# protoboard.net
KiCad netlist of a schematic drawn in EAGLE
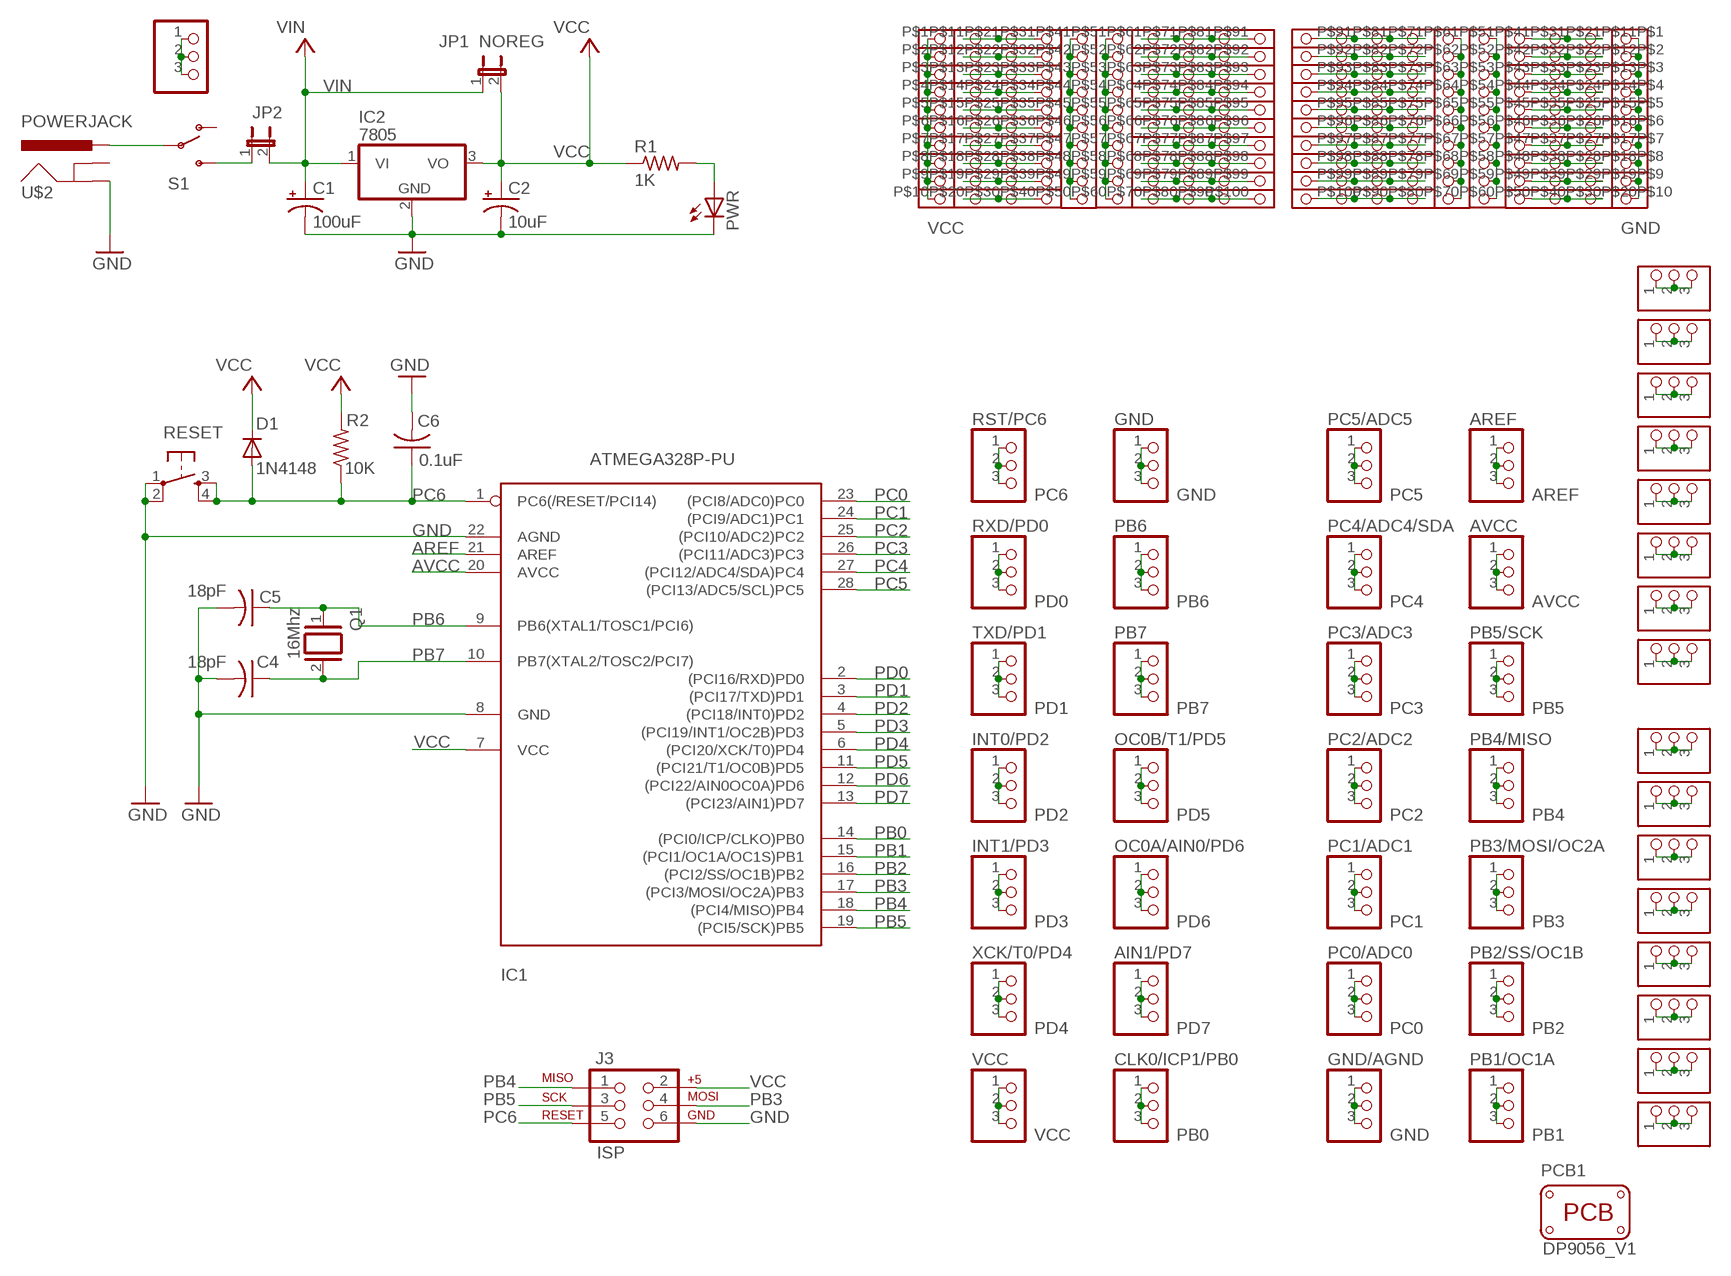
[diagram p0: schematic, sheet 1]

(export (version "E")
  (design (tool "Eeschema 10.0.6"))
  (components
    (comp (ref "AIN1/PD7")
      (value "PINHD-1X3")
      (footprint "eagle-import:1X03")
      (libsource (lib "eagle-import") (part "PINHD-1X3"))
    )
    (comp (ref "AREF")
      (value "PINHD-1X3")
      (footprint "eagle-import:1X03")
      (libsource (lib "eagle-import") (part "PINHD-1X3"))
    )
    (comp (ref "AVCC")
      (value "PINHD-1X3")
      (footprint "eagle-import:1X03")
      (libsource (lib "eagle-import") (part "PINHD-1X3"))
    )
    (comp (ref "C1")
      (value "100uF")
      (footprint "eagle-import:CPOL-RADIAL-100UF-25V")
      (libsource (lib "eagle-import") (part "CAP_POLPTH1"))
    )
    (comp (ref "C2")
      (value "10uF")
      (footprint "eagle-import:CPOL-RADIAL-10UF-25V")
      (libsource (lib "eagle-import") (part "CAP_POLPTH2"))
    )
    (comp (ref "C4")
      (value "18pF")
      (footprint "eagle-import:C025-025X050")
      (libsource (lib "eagle-import") (part "C-US025-025X050"))
    )
    (comp (ref "C5")
      (value "18pF")
      (footprint "eagle-import:C025-025X050")
      (libsource (lib "eagle-import") (part "C-US025-025X050"))
    )
    (comp (ref "C6")
      (value "0.1uF")
      (footprint "eagle-import:C025-025X050")
      (libsource (lib "eagle-import") (part "C-US025-025X050"))
    )
    (comp (ref "CLK0/ICP1/PB0")
      (value "PINHD-1X3")
      (footprint "eagle-import:1X03")
      (libsource (lib "eagle-import") (part "PINHD-1X3"))
    )
    (comp (ref "D1")
      (value "1N4148")
      (footprint "eagle-import:DIODE-1N4148")
      (libsource (lib "eagle-import") (part "DIODE1N4148"))
    )
    (comp (ref "GND")
      (value "PINHD-1X3")
      (footprint "eagle-import:1X03")
      (libsource (lib "eagle-import") (part "PINHD-1X3"))
    )
    (comp (ref "GND/AGND")
      (value "PINHD-1X3")
      (footprint "eagle-import:1X03")
      (libsource (lib "eagle-import") (part "PINHD-1X3"))
    )
    (comp (ref "IC1")
      (value "ATMEGA328P-PU")
      (footprint "eagle-import:DIL28-3")
      (libsource (lib "eagle-import") (part "ATMEGA168P-20"))
    )
    (comp (ref "IC2")
      (value "7805")
      (footprint "eagle-import:TO220H")
      (libsource (lib "eagle-import") (part "78T05"))
    )
    (comp (ref "INT0/PD2")
      (value "PINHD-1X3")
      (footprint "eagle-import:1X03")
      (libsource (lib "eagle-import") (part "PINHD-1X3"))
    )
    (comp (ref "INT1/PD3")
      (value "PINHD-1X3")
      (footprint "eagle-import:1X03")
      (libsource (lib "eagle-import") (part "PINHD-1X3"))
    )
    (comp (ref "J3")
      (value "ISP")
      (footprint "eagle-import:2X3")
      (libsource (lib "eagle-import") (part "AVR_SPI_PRG_6PTH"))
    )
    (comp (ref "JP1")
      (value "NOREG")
      (footprint "eagle-import:1X02")
      (libsource (lib "eagle-import") (part "JUMPER-2PTH"))
    )
    (comp (ref "JP2")
      (value "TP1")
      (footprint "eagle-import:1X02")
      (libsource (lib "eagle-import") (part "JUMPER-2PTH"))
    )
    (comp (ref "OC0A/AIN0/PD6")
      (value "PINHD-1X3")
      (footprint "eagle-import:1X03")
      (libsource (lib "eagle-import") (part "PINHD-1X3"))
    )
    (comp (ref "OC0B/T1/PD5")
      (value "PINHD-1X3")
      (footprint "eagle-import:1X03")
      (libsource (lib "eagle-import") (part "PINHD-1X3"))
    )
    (comp (ref "PB1/OC1A")
      (value "PINHD-1X3")
      (footprint "eagle-import:1X03")
      (libsource (lib "eagle-import") (part "PINHD-1X3"))
    )
    (comp (ref "PB2/SS/OC1B")
      (value "PINHD-1X3")
      (footprint "eagle-import:1X03")
      (libsource (lib "eagle-import") (part "PINHD-1X3"))
    )
    (comp (ref "PB3/MOSI/OC2A")
      (value "PINHD-1X3")
      (footprint "eagle-import:1X03")
      (libsource (lib "eagle-import") (part "PINHD-1X3"))
    )
    (comp (ref "PB4/MISO")
      (value "PINHD-1X3")
      (footprint "eagle-import:1X03")
      (libsource (lib "eagle-import") (part "PINHD-1X3"))
    )
    (comp (ref "PB5/SCK")
      (value "PINHD-1X3")
      (footprint "eagle-import:1X03")
      (libsource (lib "eagle-import") (part "PINHD-1X3"))
    )
    (comp (ref "PB6")
      (value "PINHD-1X3")
      (footprint "eagle-import:1X03")
      (libsource (lib "eagle-import") (part "PINHD-1X3"))
    )
    (comp (ref "PB7")
      (value "PINHD-1X3")
      (footprint "eagle-import:1X03")
      (libsource (lib "eagle-import") (part "PINHD-1X3"))
    )
    (comp (ref "PC0/ADC0")
      (value "PINHD-1X3")
      (footprint "eagle-import:1X03")
      (libsource (lib "eagle-import") (part "PINHD-1X3"))
    )
    (comp (ref "PC1/ADC1")
      (value "PINHD-1X3")
      (footprint "eagle-import:1X03")
      (libsource (lib "eagle-import") (part "PINHD-1X3"))
    )
    (comp (ref "PC2/ADC2")
      (value "PINHD-1X3")
      (footprint "eagle-import:1X03")
      (libsource (lib "eagle-import") (part "PINHD-1X3"))
    )
    (comp (ref "PC3/ADC3")
      (value "PINHD-1X3")
      (footprint "eagle-import:1X03")
      (libsource (lib "eagle-import") (part "PINHD-1X3"))
    )
    (comp (ref "PC4/ADC4/SDA")
      (value "PINHD-1X3")
      (footprint "eagle-import:1X03")
      (libsource (lib "eagle-import") (part "PINHD-1X3"))
    )
    (comp (ref "PC5/ADC5")
      (value "PINHD-1X3")
      (footprint "eagle-import:1X03")
      (libsource (lib "eagle-import") (part "PINHD-1X3"))
    )
    (comp (ref "PCB1")
      (value "PCB_DP_RECTANGLE-56X90")
      (footprint "eagle-import:DP9056_V1")
      (libsource (lib "eagle-import") (part "PCB_DP_RECTANGLE-56X90"))
    )
    (comp (ref "PWR")
      (value "LED3MM")
      (footprint "eagle-import:LED3MM")
      (libsource (lib "eagle-import") (part "LED3MM"))
    )
    (comp (ref "Q1")
      (value "16Mhz")
      (footprint "eagle-import:QS")
      (libsource (lib "eagle-import") (part "XTAL/S"))
    )
    (comp (ref "R1")
      (value "1K")
      (footprint "eagle-import:0207_7")
      (libsource (lib "eagle-import") (part "RESISTOR-1/4W"))
    )
    (comp (ref "R2")
      (value "10K")
      (footprint "eagle-import:0207_7")
      (libsource (lib "eagle-import") (part "RESISTOR-1/4W"))
    )
    (comp (ref "RESET")
      (value "TAC_SWITCHPTH")
      (footprint "eagle-import:TACTILE-PTH")
      (libsource (lib "eagle-import") (part "TAC_SWITCHPTH"))
    )
    (comp (ref "RST/PC6")
      (value "PINHD-1X3")
      (footprint "eagle-import:1X03")
      (libsource (lib "eagle-import") (part "PINHD-1X3"))
    )
    (comp (ref "RXD/PD0")
      (value "PINHD-1X3")
      (footprint "eagle-import:1X03")
      (libsource (lib "eagle-import") (part "PINHD-1X3"))
    )
    (comp (ref "S1")
      (value "SWITCH-SPDTPTH")
      (footprint "eagle-import:SWITCH-SPDT")
      (libsource (lib "eagle-import") (part "SWITCH-SPDTPTH"))
    )
    (comp (ref "TXD/PD1")
      (value "PINHD-1X3")
      (footprint "eagle-import:1X03")
      (libsource (lib "eagle-import") (part "PINHD-1X3"))
    )
    (comp (ref "U$1")
      (value "PROTOFIELD-10X10")
      (footprint "eagle-import:PROTOFIELD-10X10")
      (libsource (lib "eagle-import") (part "PROTOFIELD-10X10"))
    )
    (comp (ref "U$2")
      (value "POWERJACK")
      (footprint "eagle-import:POWERJACK_SLOT")
      (libsource (lib "eagle-import") (part "POWERJACK"))
    )
    (comp (ref "U$3")
      (value "PROTOFIELD-10X10")
      (footprint "eagle-import:PROTOFIELD-10X10")
      (libsource (lib "eagle-import") (part "PROTOFIELD-10X10"))
    )
    (comp (ref "U$4")
      (value "PROTOFIELD-3")
      (footprint "eagle-import:PROTOFIELD-3")
      (libsource (lib "eagle-import") (part "PROTOFIELD-3"))
    )
    (comp (ref "U$5")
      (value "PROTOFIELD-3")
      (footprint "eagle-import:PROTOFIELD-3")
      (libsource (lib "eagle-import") (part "PROTOFIELD-3"))
    )
    (comp (ref "U$6")
      (value "PROTOFIELD-3")
      (footprint "eagle-import:PROTOFIELD-3")
      (libsource (lib "eagle-import") (part "PROTOFIELD-3"))
    )
    (comp (ref "U$7")
      (value "PROTOFIELD-3")
      (footprint "eagle-import:PROTOFIELD-3")
      (libsource (lib "eagle-import") (part "PROTOFIELD-3"))
    )
    (comp (ref "U$8")
      (value "PROTOFIELD-3")
      (footprint "eagle-import:PROTOFIELD-3")
      (libsource (lib "eagle-import") (part "PROTOFIELD-3"))
    )
    (comp (ref "U$9")
      (value "PROTOFIELD-3")
      (footprint "eagle-import:PROTOFIELD-3")
      (libsource (lib "eagle-import") (part "PROTOFIELD-3"))
    )
    (comp (ref "U$10")
      (value "PROTOFIELD-3")
      (footprint "eagle-import:PROTOFIELD-3")
      (libsource (lib "eagle-import") (part "PROTOFIELD-3"))
    )
    (comp (ref "U$11")
      (value "PROTOFIELD-3")
      (footprint "eagle-import:PROTOFIELD-3")
      (libsource (lib "eagle-import") (part "PROTOFIELD-3"))
    )
    (comp (ref "U$12")
      (value "PROTOFIELD-3")
      (footprint "eagle-import:PROTOFIELD-3")
      (libsource (lib "eagle-import") (part "PROTOFIELD-3"))
    )
    (comp (ref "U$13")
      (value "PROTOFIELD-3")
      (footprint "eagle-import:PROTOFIELD-3")
      (libsource (lib "eagle-import") (part "PROTOFIELD-3"))
    )
    (comp (ref "U$14")
      (value "PROTOFIELD-3")
      (footprint "eagle-import:PROTOFIELD-3")
      (libsource (lib "eagle-import") (part "PROTOFIELD-3"))
    )
    (comp (ref "U$15")
      (value "PROTOFIELD-3")
      (footprint "eagle-import:PROTOFIELD-3")
      (libsource (lib "eagle-import") (part "PROTOFIELD-3"))
    )
    (comp (ref "U$16")
      (value "PROTOFIELD-3")
      (footprint "eagle-import:PROTOFIELD-3")
      (libsource (lib "eagle-import") (part "PROTOFIELD-3"))
    )
    (comp (ref "U$17")
      (value "PROTOFIELD-3")
      (footprint "eagle-import:PROTOFIELD-3")
      (libsource (lib "eagle-import") (part "PROTOFIELD-3"))
    )
    (comp (ref "U$18")
      (value "PROTOFIELD-3")
      (footprint "eagle-import:PROTOFIELD-3")
      (libsource (lib "eagle-import") (part "PROTOFIELD-3"))
    )
    (comp (ref "U$19")
      (value "PROTOFIELD-3")
      (footprint "eagle-import:PROTOFIELD-3")
      (libsource (lib "eagle-import") (part "PROTOFIELD-3"))
    )
    (comp (ref "VCC")
      (value "PINHD-1X3")
      (footprint "eagle-import:1X03")
      (libsource (lib "eagle-import") (part "PINHD-1X3"))
    )
    (comp (ref "VIN_")
      (value "PINHD-1X3")
      (footprint "eagle-import:1X03")
      (libsource (lib "eagle-import") (part "PINHD-1X3"))
    )
    (comp (ref "XCK/T0/PD4")
      (value "PINHD-1X3")
      (footprint "eagle-import:1X03")
      (libsource (lib "eagle-import") (part "PINHD-1X3"))
    )
  )
  (nets
    (net (code "1") (name "/AREF") (class "Default")
      (node (ref "AREF") (pin "1") (pinfunction "1_1") (pintype "passive"))
      (node (ref "AREF") (pin "2") (pinfunction "2_2") (pintype "passive"))
      (node (ref "AREF") (pin "3") (pinfunction "3_3") (pintype "passive"))
      (node (ref "IC1") (pin "21") (pinfunction "AREF_21") (pintype "bidirectional"))
    )
    (net (code "2") (name "/AVCC") (class "Default")
      (node (ref "AVCC") (pin "1") (pinfunction "1_1") (pintype "passive"))
      (node (ref "AVCC") (pin "2") (pinfunction "2_2") (pintype "passive"))
      (node (ref "AVCC") (pin "3") (pinfunction "3_3") (pintype "passive"))
      (node (ref "IC1") (pin "20") (pinfunction "AVCC_20") (pintype "bidirectional"))
    )
    (net (code "3") (name "/PB0") (class "Default")
      (node (ref "CLK0/ICP1/PB0") (pin "1") (pinfunction "1_1") (pintype "passive"))
      (node (ref "CLK0/ICP1/PB0") (pin "2") (pinfunction "2_2") (pintype "passive"))
      (node (ref "CLK0/ICP1/PB0") (pin "3") (pinfunction "3_3") (pintype "passive"))
      (node (ref "IC1") (pin "14") (pinfunction "(PCI0/ICP/CLKO)PB0_14") (pintype "bidirectional"))
    )
    (net (code "4") (name "/PB1") (class "Default")
      (node (ref "IC1") (pin "15") (pinfunction "(PCI1/OC1A/OC1S)PB1_15") (pintype "bidirectional"))
      (node (ref "PB1/OC1A") (pin "1") (pinfunction "1_1") (pintype "passive"))
      (node (ref "PB1/OC1A") (pin "2") (pinfunction "2_2") (pintype "passive"))
      (node (ref "PB1/OC1A") (pin "3") (pinfunction "3_3") (pintype "passive"))
    )
    (net (code "5") (name "/PB2") (class "Default")
      (node (ref "IC1") (pin "16") (pinfunction "(PCI2/SS/OC1B)PB2_16") (pintype "bidirectional"))
      (node (ref "PB2/SS/OC1B") (pin "1") (pinfunction "1_1") (pintype "passive"))
      (node (ref "PB2/SS/OC1B") (pin "2") (pinfunction "2_2") (pintype "passive"))
      (node (ref "PB2/SS/OC1B") (pin "3") (pinfunction "3_3") (pintype "passive"))
    )
    (net (code "6") (name "/PB3") (class "Default")
      (node (ref "IC1") (pin "17") (pinfunction "(PCI3/MOSI/OC2A)PB3_17") (pintype "bidirectional"))
      (node (ref "J3") (pin "4") (pinfunction "4_4") (pintype "passive"))
      (node (ref "PB3/MOSI/OC2A") (pin "1") (pinfunction "1_1") (pintype "passive"))
      (node (ref "PB3/MOSI/OC2A") (pin "2") (pinfunction "2_2") (pintype "passive"))
      (node (ref "PB3/MOSI/OC2A") (pin "3") (pinfunction "3_3") (pintype "passive"))
    )
    (net (code "7") (name "/PB4") (class "Default")
      (node (ref "IC1") (pin "18") (pinfunction "(PCI4/MISO)PB4_18") (pintype "bidirectional"))
      (node (ref "J3") (pin "1") (pinfunction "1_1") (pintype "passive"))
      (node (ref "PB4/MISO") (pin "1") (pinfunction "1_1") (pintype "passive"))
      (node (ref "PB4/MISO") (pin "2") (pinfunction "2_2") (pintype "passive"))
      (node (ref "PB4/MISO") (pin "3") (pinfunction "3_3") (pintype "passive"))
    )
    (net (code "8") (name "/PB5") (class "Default")
      (node (ref "IC1") (pin "19") (pinfunction "(PCI5/SCK)PB5_19") (pintype "bidirectional"))
      (node (ref "J3") (pin "3") (pinfunction "3_3") (pintype "passive"))
      (node (ref "PB5/SCK") (pin "1") (pinfunction "1_1") (pintype "passive"))
      (node (ref "PB5/SCK") (pin "2") (pinfunction "2_2") (pintype "passive"))
      (node (ref "PB5/SCK") (pin "3") (pinfunction "3_3") (pintype "passive"))
    )
    (net (code "9") (name "/PB6") (class "Default")
      (node (ref "C5") (pin "1") (pinfunction "1_1") (pintype "passive"))
      (node (ref "IC1") (pin "9") (pinfunction "PB6(XTAL1/TOSC1/PCI6)_9") (pintype "bidirectional"))
      (node (ref "PB6") (pin "1") (pinfunction "1_1") (pintype "passive"))
      (node (ref "PB6") (pin "2") (pinfunction "2_2") (pintype "passive"))
      (node (ref "PB6") (pin "3") (pinfunction "3_3") (pintype "passive"))
      (node (ref "Q1") (pin "1") (pinfunction "1_1") (pintype "passive"))
    )
    (net (code "10") (name "/PB7") (class "Default")
      (node (ref "C4") (pin "1") (pinfunction "1_1") (pintype "passive"))
      (node (ref "IC1") (pin "10") (pinfunction "PB7(XTAL2/TOSC2/PCI7)_10") (pintype "bidirectional"))
      (node (ref "PB7") (pin "1") (pinfunction "1_1") (pintype "passive"))
      (node (ref "PB7") (pin "2") (pinfunction "2_2") (pintype "passive"))
      (node (ref "PB7") (pin "3") (pinfunction "3_3") (pintype "passive"))
      (node (ref "Q1") (pin "2") (pinfunction "2_2") (pintype "passive"))
    )
    (net (code "11") (name "/PC0") (class "Default")
      (node (ref "IC1") (pin "23") (pinfunction "(PCI8/ADC0)PC0_23") (pintype "bidirectional"))
      (node (ref "PC0/ADC0") (pin "1") (pinfunction "1_1") (pintype "passive"))
      (node (ref "PC0/ADC0") (pin "2") (pinfunction "2_2") (pintype "passive"))
      (node (ref "PC0/ADC0") (pin "3") (pinfunction "3_3") (pintype "passive"))
    )
    (net (code "12") (name "/PC1") (class "Default")
      (node (ref "IC1") (pin "24") (pinfunction "(PCI9/ADC1)PC1_24") (pintype "bidirectional"))
      (node (ref "PC1/ADC1") (pin "1") (pinfunction "1_1") (pintype "passive"))
      (node (ref "PC1/ADC1") (pin "2") (pinfunction "2_2") (pintype "passive"))
      (node (ref "PC1/ADC1") (pin "3") (pinfunction "3_3") (pintype "passive"))
    )
    (net (code "13") (name "/PC2") (class "Default")
      (node (ref "IC1") (pin "25") (pinfunction "(PCI10/ADC2)PC2_25") (pintype "bidirectional"))
      (node (ref "PC2/ADC2") (pin "1") (pinfunction "1_1") (pintype "passive"))
      (node (ref "PC2/ADC2") (pin "2") (pinfunction "2_2") (pintype "passive"))
      (node (ref "PC2/ADC2") (pin "3") (pinfunction "3_3") (pintype "passive"))
    )
    (net (code "14") (name "/PC3") (class "Default")
      (node (ref "IC1") (pin "26") (pinfunction "(PCI11/ADC3)PC3_26") (pintype "bidirectional"))
      (node (ref "PC3/ADC3") (pin "1") (pinfunction "1_1") (pintype "passive"))
      (node (ref "PC3/ADC3") (pin "2") (pinfunction "2_2") (pintype "passive"))
      (node (ref "PC3/ADC3") (pin "3") (pinfunction "3_3") (pintype "passive"))
    )
    (net (code "15") (name "/PC4") (class "Default")
      (node (ref "IC1") (pin "27") (pinfunction "(PCI12/ADC4/SDA)PC4_27") (pintype "bidirectional"))
      (node (ref "PC4/ADC4/SDA") (pin "1") (pinfunction "1_1") (pintype "passive"))
      (node (ref "PC4/ADC4/SDA") (pin "2") (pinfunction "2_2") (pintype "passive"))
      (node (ref "PC4/ADC4/SDA") (pin "3") (pinfunction "3_3") (pintype "passive"))
    )
    (net (code "16") (name "/PC5") (class "Default")
      (node (ref "IC1") (pin "28") (pinfunction "(PCI13/ADC5/SCL)PC5_28") (pintype "bidirectional"))
      (node (ref "PC5/ADC5") (pin "1") (pinfunction "1_1") (pintype "passive"))
      (node (ref "PC5/ADC5") (pin "2") (pinfunction "2_2") (pintype "passive"))
      (node (ref "PC5/ADC5") (pin "3") (pinfunction "3_3") (pintype "passive"))
    )
    (net (code "17") (name "/PC6") (class "Default")
      (node (ref "C6") (pin "1") (pinfunction "1_1") (pintype "passive"))
      (node (ref "D1") (pin "A") (pinfunction "A_A") (pintype "passive"))
      (node (ref "IC1") (pin "1") (pinfunction "PC6(/RESET/PCI14)_1") (pintype "bidirectional"))
      (node (ref "J3") (pin "5") (pinfunction "5_5") (pintype "passive"))
      (node (ref "R2") (pin "1") (pinfunction "1_1") (pintype "passive"))
      (node (ref "RESET") (pin "3") (pinfunction "3_3") (pintype "passive"))
      (node (ref "RESET") (pin "4") (pinfunction "4_4") (pintype "passive"))
      (node (ref "RST/PC6") (pin "1") (pinfunction "1_1") (pintype "passive"))
      (node (ref "RST/PC6") (pin "2") (pinfunction "2_2") (pintype "passive"))
      (node (ref "RST/PC6") (pin "3") (pinfunction "3_3") (pintype "passive"))
    )
    (net (code "18") (name "/PD0") (class "Default")
      (node (ref "IC1") (pin "2") (pinfunction "(PCI16/RXD)PD0_2") (pintype "bidirectional"))
      (node (ref "RXD/PD0") (pin "1") (pinfunction "1_1") (pintype "passive"))
      (node (ref "RXD/PD0") (pin "2") (pinfunction "2_2") (pintype "passive"))
      (node (ref "RXD/PD0") (pin "3") (pinfunction "3_3") (pintype "passive"))
    )
    (net (code "19") (name "/PD1") (class "Default")
      (node (ref "IC1") (pin "3") (pinfunction "(PCI17/TXD)PD1_3") (pintype "bidirectional"))
      (node (ref "TXD/PD1") (pin "1") (pinfunction "1_1") (pintype "passive"))
      (node (ref "TXD/PD1") (pin "2") (pinfunction "2_2") (pintype "passive"))
      (node (ref "TXD/PD1") (pin "3") (pinfunction "3_3") (pintype "passive"))
    )
    (net (code "20") (name "/PD2") (class "Default")
      (node (ref "IC1") (pin "4") (pinfunction "(PCI18/INT0)PD2_4") (pintype "bidirectional"))
      (node (ref "INT0/PD2") (pin "1") (pinfunction "1_1") (pintype "passive"))
      (node (ref "INT0/PD2") (pin "2") (pinfunction "2_2") (pintype "passive"))
      (node (ref "INT0/PD2") (pin "3") (pinfunction "3_3") (pintype "passive"))
    )
    (net (code "21") (name "/PD3") (class "Default")
      (node (ref "IC1") (pin "5") (pinfunction "(PCI19/INT1/OC2B)PD3_5") (pintype "bidirectional"))
      (node (ref "INT1/PD3") (pin "1") (pinfunction "1_1") (pintype "passive"))
      (node (ref "INT1/PD3") (pin "2") (pinfunction "2_2") (pintype "passive"))
      (node (ref "INT1/PD3") (pin "3") (pinfunction "3_3") (pintype "passive"))
    )
    (net (code "22") (name "/PD4") (class "Default")
      (node (ref "IC1") (pin "6") (pinfunction "(PCI20/XCK/T0)PD4_6") (pintype "bidirectional"))
      (node (ref "XCK/T0/PD4") (pin "1") (pinfunction "1_1") (pintype "passive"))
      (node (ref "XCK/T0/PD4") (pin "2") (pinfunction "2_2") (pintype "passive"))
      (node (ref "XCK/T0/PD4") (pin "3") (pinfunction "3_3") (pintype "passive"))
    )
    (net (code "23") (name "/PD5") (class "Default")
      (node (ref "IC1") (pin "11") (pinfunction "(PCI21/T1/OC0B)PD5_11") (pintype "bidirectional"))
      (node (ref "OC0B/T1/PD5") (pin "1") (pinfunction "1_1") (pintype "passive"))
      (node (ref "OC0B/T1/PD5") (pin "2") (pinfunction "2_2") (pintype "passive"))
      (node (ref "OC0B/T1/PD5") (pin "3") (pinfunction "3_3") (pintype "passive"))
    )
    (net (code "24") (name "/PD6") (class "Default")
      (node (ref "IC1") (pin "12") (pinfunction "(PCI22/AIN0OC0A)PD6_12") (pintype "bidirectional"))
      (node (ref "OC0A/AIN0/PD6") (pin "1") (pinfunction "1_1") (pintype "passive"))
      (node (ref "OC0A/AIN0/PD6") (pin "2") (pinfunction "2_2") (pintype "passive"))
      (node (ref "OC0A/AIN0/PD6") (pin "3") (pinfunction "3_3") (pintype "passive"))
    )
    (net (code "25") (name "/PD7") (class "Default")
      (node (ref "AIN1/PD7") (pin "1") (pinfunction "1_1") (pintype "passive"))
      (node (ref "AIN1/PD7") (pin "2") (pinfunction "2_2") (pintype "passive"))
      (node (ref "AIN1/PD7") (pin "3") (pinfunction "3_3") (pintype "passive"))
      (node (ref "IC1") (pin "13") (pinfunction "(PCI23/AIN1)PD7_13") (pintype "bidirectional"))
    )
    (net (code "26") (name "GND") (class "Default")
      (node (ref "C1") (pin "2") (pinfunction "-_2") (pintype "passive"))
      (node (ref "C2") (pin "2") (pinfunction "-_2") (pintype "passive"))
      (node (ref "C4") (pin "2") (pinfunction "2_2") (pintype "passive"))
      (node (ref "C5") (pin "2") (pinfunction "2_2") (pintype "passive"))
      (node (ref "C6") (pin "2") (pinfunction "2_2") (pintype "passive"))
      (node (ref "GND") (pin "1") (pinfunction "1_1") (pintype "passive"))
      (node (ref "GND") (pin "2") (pinfunction "2_2") (pintype "passive"))
      (node (ref "GND") (pin "3") (pinfunction "3_3") (pintype "passive"))
      (node (ref "GND/AGND") (pin "1") (pinfunction "1_1") (pintype "passive"))
      (node (ref "GND/AGND") (pin "2") (pinfunction "2_2") (pintype "passive"))
      (node (ref "GND/AGND") (pin "3") (pinfunction "3_3") (pintype "passive"))
      (node (ref "IC1") (pin "22") (pinfunction "AGND_22") (pintype "bidirectional"))
      (node (ref "IC1") (pin "8") (pinfunction "GND_8") (pintype "bidirectional"))
      (node (ref "IC2") (pin "2") (pinfunction "GND_2") (pintype "passive"))
      (node (ref "J3") (pin "6") (pinfunction "6_6") (pintype "passive"))
      (node (ref "PWR") (pin "K") (pinfunction "C_K") (pintype "passive"))
      (node (ref "RESET") (pin "1") (pinfunction "1_1") (pintype "passive"))
      (node (ref "RESET") (pin "2") (pinfunction "2_2") (pintype "passive"))
      (node (ref "U$2") (pin "GND@1") (pinfunction "GND_GND@1") (pintype "bidirectional"))
      (node (ref "U$3") (pin "P$1") (pinfunction "1_P$1") (pintype "passive"))
      (node (ref "U$3") (pin "P$10") (pinfunction "P$10_P$10") (pintype "passive"))
      (node (ref "U$3") (pin "P$2") (pinfunction "5_P$2") (pintype "passive"))
      (node (ref "U$3") (pin "P$3") (pinfunction "P$3_P$3") (pintype "passive"))
      (node (ref "U$3") (pin "P$4") (pinfunction "P$4_P$4") (pintype "passive"))
      (node (ref "U$3") (pin "P$5") (pinfunction "P$5_P$5") (pintype "passive"))
      (node (ref "U$3") (pin "P$6") (pinfunction "P$6_P$6") (pintype "passive"))
      (node (ref "U$3") (pin "P$7") (pinfunction "P$7_P$7") (pintype "passive"))
      (node (ref "U$3") (pin "P$8") (pinfunction "P$8_P$8") (pintype "passive"))
      (node (ref "U$3") (pin "P$9") (pinfunction "P$9_P$9") (pintype "passive"))
    )
    (net (code "27") (name "Net-(PWR-PadA)") (class "Default")
      (node (ref "PWR") (pin "A") (pinfunction "A_A") (pintype "passive"))
      (node (ref "R1") (pin "2") (pinfunction "2_2") (pintype "passive"))
    )
    (net (code "28") (name "Net-(S1-P)") (class "Default")
      (node (ref "S1") (pin "2") (pinfunction "P_2") (pintype "passive"))
      (node (ref "U$2") (pin "PWR") (pinfunction "PWR_PWR") (pintype "bidirectional"))
    )
    (net (code "29") (name "Net-(S1-S)") (class "Default")
      (node (ref "JP2") (pin "1") (pinfunction "1_1") (pintype "passive"))
      (node (ref "S1") (pin "3") (pinfunction "S_3") (pintype "passive"))
    )
    (net (code "30") (name "Net-(U$1-2)") (class "Default")
      (node (ref "U$1") (pin "P$11") (pinfunction "2_P$11") (pintype "passive"))
      (node (ref "U$1") (pin "P$21") (pinfunction "3_P$21") (pintype "passive"))
      (node (ref "U$1") (pin "P$31") (pinfunction "4_P$31") (pintype "passive"))
    )
    (net (code "31") (name "Net-(U$1-6)") (class "Default")
      (node (ref "U$1") (pin "P$12") (pinfunction "6_P$12") (pintype "passive"))
      (node (ref "U$1") (pin "P$22") (pinfunction "7_P$22") (pintype "passive"))
      (node (ref "U$1") (pin "P$32") (pinfunction "8_P$32") (pintype "passive"))
    )
    (net (code "32") (name "Net-(U$1-PadP$13)") (class "Default")
      (node (ref "U$1") (pin "P$13") (pinfunction "P$13_P$13") (pintype "passive"))
      (node (ref "U$1") (pin "P$23") (pinfunction "P$23_P$23") (pintype "passive"))
      (node (ref "U$1") (pin "P$33") (pinfunction "P$33_P$33") (pintype "passive"))
    )
    (net (code "33") (name "Net-(U$1-PadP$14)") (class "Default")
      (node (ref "U$1") (pin "P$14") (pinfunction "P$14_P$14") (pintype "passive"))
      (node (ref "U$1") (pin "P$24") (pinfunction "P$24_P$24") (pintype "passive"))
      (node (ref "U$1") (pin "P$34") (pinfunction "P$34_P$34") (pintype "passive"))
    )
    (net (code "34") (name "Net-(U$1-PadP$15)") (class "Default")
      (node (ref "U$1") (pin "P$15") (pinfunction "P$15_P$15") (pintype "passive"))
      (node (ref "U$1") (pin "P$25") (pinfunction "P$25_P$25") (pintype "passive"))
      (node (ref "U$1") (pin "P$35") (pinfunction "P$35_P$35") (pintype "passive"))
    )
    (net (code "35") (name "Net-(U$1-PadP$16)") (class "Default")
      (node (ref "U$1") (pin "P$16") (pinfunction "P$16_P$16") (pintype "passive"))
      (node (ref "U$1") (pin "P$26") (pinfunction "P$26_P$26") (pintype "passive"))
      (node (ref "U$1") (pin "P$36") (pinfunction "P$36_P$36") (pintype "passive"))
    )
    (net (code "36") (name "Net-(U$1-PadP$17)") (class "Default")
      (node (ref "U$1") (pin "P$17") (pinfunction "P$17_P$17") (pintype "passive"))
      (node (ref "U$1") (pin "P$27") (pinfunction "P$27_P$27") (pintype "passive"))
      (node (ref "U$1") (pin "P$37") (pinfunction "P$37_P$37") (pintype "passive"))
    )
    (net (code "37") (name "Net-(U$1-PadP$18)") (class "Default")
      (node (ref "U$1") (pin "P$18") (pinfunction "P$18_P$18") (pintype "passive"))
      (node (ref "U$1") (pin "P$28") (pinfunction "P$28_P$28") (pintype "passive"))
      (node (ref "U$1") (pin "P$38") (pinfunction "P$38_P$38") (pintype "passive"))
    )
    (net (code "38") (name "Net-(U$1-PadP$19)") (class "Default")
      (node (ref "U$1") (pin "P$19") (pinfunction "P$19_P$19") (pintype "passive"))
      (node (ref "U$1") (pin "P$29") (pinfunction "P$29_P$29") (pintype "passive"))
      (node (ref "U$1") (pin "P$39") (pinfunction "P$39_P$39") (pintype "passive"))
    )
    (net (code "39") (name "Net-(U$1-PadP$20)") (class "Default")
      (node (ref "U$1") (pin "P$20") (pinfunction "P$20_P$20") (pintype "passive"))
      (node (ref "U$1") (pin "P$30") (pinfunction "P$30_P$30") (pintype "passive"))
      (node (ref "U$1") (pin "P$40") (pinfunction "P$40_P$40") (pintype "passive"))
    )
    (net (code "40") (name "Net-(U$1-PadP$41)") (class "Default")
      (node (ref "U$1") (pin "P$41") (pinfunction "P$41_P$41") (pintype "passive"))
      (node (ref "U$1") (pin "P$42") (pinfunction "P$42_P$42") (pintype "passive"))
      (node (ref "U$1") (pin "P$43") (pinfunction "P$43_P$43") (pintype "passive"))
      (node (ref "U$1") (pin "P$44") (pinfunction "P$44_P$44") (pintype "passive"))
      (node (ref "U$1") (pin "P$45") (pinfunction "P$45_P$45") (pintype "passive"))
      (node (ref "U$1") (pin "P$46") (pinfunction "P$46_P$46") (pintype "passive"))
      (node (ref "U$1") (pin "P$47") (pinfunction "P$47_P$47") (pintype "passive"))
      (node (ref "U$1") (pin "P$48") (pinfunction "P$48_P$48") (pintype "passive"))
      (node (ref "U$1") (pin "P$49") (pinfunction "P$49_P$49") (pintype "passive"))
      (node (ref "U$1") (pin "P$50") (pinfunction "P$50_P$50") (pintype "passive"))
    )
    (net (code "41") (name "Net-(U$1-PadP$51)") (class "Default")
      (node (ref "U$1") (pin "P$51") (pinfunction "P$51_P$51") (pintype "passive"))
      (node (ref "U$1") (pin "P$52") (pinfunction "P$52_P$52") (pintype "passive"))
      (node (ref "U$1") (pin "P$53") (pinfunction "P$53_P$53") (pintype "passive"))
      (node (ref "U$1") (pin "P$54") (pinfunction "P$54_P$54") (pintype "passive"))
      (node (ref "U$1") (pin "P$55") (pinfunction "P$55_P$55") (pintype "passive"))
      (node (ref "U$1") (pin "P$56") (pinfunction "P$56_P$56") (pintype "passive"))
      (node (ref "U$1") (pin "P$57") (pinfunction "P$57_P$57") (pintype "passive"))
      (node (ref "U$1") (pin "P$58") (pinfunction "P$58_P$58") (pintype "passive"))
      (node (ref "U$1") (pin "P$59") (pinfunction "P$59_P$59") (pintype "passive"))
      (node (ref "U$1") (pin "P$60") (pinfunction "P$60_P$60") (pintype "passive"))
    )
    (net (code "42") (name "Net-(U$1-PadP$61)") (class "Default")
      (node (ref "U$1") (pin "P$61") (pinfunction "P$61_P$61") (pintype "passive"))
      (node (ref "U$1") (pin "P$71") (pinfunction "P$71_P$71") (pintype "passive"))
      (node (ref "U$1") (pin "P$81") (pinfunction "P$81_P$81") (pintype "passive"))
      (node (ref "U$1") (pin "P$91") (pinfunction "P$91_P$91") (pintype "passive"))
    )
    (net (code "43") (name "Net-(U$1-PadP$62)") (class "Default")
      (node (ref "U$1") (pin "P$62") (pinfunction "P$62_P$62") (pintype "passive"))
      (node (ref "U$1") (pin "P$72") (pinfunction "P$72_P$72") (pintype "passive"))
      (node (ref "U$1") (pin "P$82") (pinfunction "P$82_P$82") (pintype "passive"))
      (node (ref "U$1") (pin "P$92") (pinfunction "P$92_P$92") (pintype "passive"))
    )
    (net (code "44") (name "Net-(U$1-PadP$63)") (class "Default")
      (node (ref "U$1") (pin "P$63") (pinfunction "P$63_P$63") (pintype "passive"))
      (node (ref "U$1") (pin "P$73") (pinfunction "P$73_P$73") (pintype "passive"))
      (node (ref "U$1") (pin "P$83") (pinfunction "P$83_P$83") (pintype "passive"))
      (node (ref "U$1") (pin "P$93") (pinfunction "P$93_P$93") (pintype "passive"))
    )
    (net (code "45") (name "Net-(U$1-PadP$64)") (class "Default")
      (node (ref "U$1") (pin "P$64") (pinfunction "P$64_P$64") (pintype "passive"))
      (node (ref "U$1") (pin "P$74") (pinfunction "P$74_P$74") (pintype "passive"))
      (node (ref "U$1") (pin "P$84") (pinfunction "P$84_P$84") (pintype "passive"))
      (node (ref "U$1") (pin "P$94") (pinfunction "P$94_P$94") (pintype "passive"))
    )
    (net (code "46") (name "Net-(U$1-PadP$65)") (class "Default")
      (node (ref "U$1") (pin "P$65") (pinfunction "P$65_P$65") (pintype "passive"))
      (node (ref "U$1") (pin "P$75") (pinfunction "P$75_P$75") (pintype "passive"))
      (node (ref "U$1") (pin "P$85") (pinfunction "P$85_P$85") (pintype "passive"))
      (node (ref "U$1") (pin "P$95") (pinfunction "P$95_P$95") (pintype "passive"))
    )
    (net (code "47") (name "Net-(U$1-PadP$66)") (class "Default")
      (node (ref "U$1") (pin "P$66") (pinfunction "P$66_P$66") (pintype "passive"))
      (node (ref "U$1") (pin "P$76") (pinfunction "P$76_P$76") (pintype "passive"))
      (node (ref "U$1") (pin "P$86") (pinfunction "P$86_P$86") (pintype "passive"))
      (node (ref "U$1") (pin "P$96") (pinfunction "P$96_P$96") (pintype "passive"))
    )
    (net (code "48") (name "Net-(U$1-PadP$67)") (class "Default")
      (node (ref "U$1") (pin "P$67") (pinfunction "P$67_P$67") (pintype "passive"))
      (node (ref "U$1") (pin "P$77") (pinfunction "P$77_P$77") (pintype "passive"))
      (node (ref "U$1") (pin "P$87") (pinfunction "P$87_P$87") (pintype "passive"))
      (node (ref "U$1") (pin "P$97") (pinfunction "P$97_P$97") (pintype "passive"))
    )
    (net (code "49") (name "Net-(U$1-PadP$68)") (class "Default")
      (node (ref "U$1") (pin "P$68") (pinfunction "P$68_P$68") (pintype "passive"))
      (node (ref "U$1") (pin "P$78") (pinfunction "P$78_P$78") (pintype "passive"))
      (node (ref "U$1") (pin "P$88") (pinfunction "P$88_P$88") (pintype "passive"))
      (node (ref "U$1") (pin "P$98") (pinfunction "P$98_P$98") (pintype "passive"))
    )
    (net (code "50") (name "Net-(U$1-PadP$69)") (class "Default")
      (node (ref "U$1") (pin "P$69") (pinfunction "P$69_P$69") (pintype "passive"))
      (node (ref "U$1") (pin "P$79") (pinfunction "P$79_P$79") (pintype "passive"))
      (node (ref "U$1") (pin "P$89") (pinfunction "P$89_P$89") (pintype "passive"))
      (node (ref "U$1") (pin "P$99") (pinfunction "P$99_P$99") (pintype "passive"))
    )
    (net (code "51") (name "Net-(U$1-PadP$100)") (class "Default")
      (node (ref "U$1") (pin "P$100") (pinfunction "P$100_P$100") (pintype "passive"))
      (node (ref "U$1") (pin "P$70") (pinfunction "P$70_P$70") (pintype "passive"))
      (node (ref "U$1") (pin "P$80") (pinfunction "P$80_P$80") (pintype "passive"))
      (node (ref "U$1") (pin "P$90") (pinfunction "P$90_P$90") (pintype "passive"))
    )
    (net (code "52") (name "Net-(U$3-2)") (class "Default")
      (node (ref "U$3") (pin "P$11") (pinfunction "2_P$11") (pintype "passive"))
      (node (ref "U$3") (pin "P$21") (pinfunction "3_P$21") (pintype "passive"))
      (node (ref "U$3") (pin "P$31") (pinfunction "4_P$31") (pintype "passive"))
    )
    (net (code "53") (name "Net-(U$3-6)") (class "Default")
      (node (ref "U$3") (pin "P$12") (pinfunction "6_P$12") (pintype "passive"))
      (node (ref "U$3") (pin "P$22") (pinfunction "7_P$22") (pintype "passive"))
      (node (ref "U$3") (pin "P$32") (pinfunction "8_P$32") (pintype "passive"))
    )
    (net (code "54") (name "Net-(U$3-PadP$13)") (class "Default")
      (node (ref "U$3") (pin "P$13") (pinfunction "P$13_P$13") (pintype "passive"))
      (node (ref "U$3") (pin "P$23") (pinfunction "P$23_P$23") (pintype "passive"))
      (node (ref "U$3") (pin "P$33") (pinfunction "P$33_P$33") (pintype "passive"))
    )
    (net (code "55") (name "Net-(U$3-PadP$14)") (class "Default")
      (node (ref "U$3") (pin "P$14") (pinfunction "P$14_P$14") (pintype "passive"))
      (node (ref "U$3") (pin "P$24") (pinfunction "P$24_P$24") (pintype "passive"))
      (node (ref "U$3") (pin "P$34") (pinfunction "P$34_P$34") (pintype "passive"))
    )
    (net (code "56") (name "Net-(U$3-PadP$15)") (class "Default")
      (node (ref "U$3") (pin "P$15") (pinfunction "P$15_P$15") (pintype "passive"))
      (node (ref "U$3") (pin "P$25") (pinfunction "P$25_P$25") (pintype "passive"))
      (node (ref "U$3") (pin "P$35") (pinfunction "P$35_P$35") (pintype "passive"))
    )
    (net (code "57") (name "Net-(U$3-PadP$16)") (class "Default")
      (node (ref "U$3") (pin "P$16") (pinfunction "P$16_P$16") (pintype "passive"))
      (node (ref "U$3") (pin "P$26") (pinfunction "P$26_P$26") (pintype "passive"))
      (node (ref "U$3") (pin "P$36") (pinfunction "P$36_P$36") (pintype "passive"))
    )
    (net (code "58") (name "Net-(U$3-PadP$17)") (class "Default")
      (node (ref "U$3") (pin "P$17") (pinfunction "P$17_P$17") (pintype "passive"))
      (node (ref "U$3") (pin "P$27") (pinfunction "P$27_P$27") (pintype "passive"))
      (node (ref "U$3") (pin "P$37") (pinfunction "P$37_P$37") (pintype "passive"))
    )
    (net (code "59") (name "Net-(U$3-PadP$18)") (class "Default")
      (node (ref "U$3") (pin "P$18") (pinfunction "P$18_P$18") (pintype "passive"))
      (node (ref "U$3") (pin "P$28") (pinfunction "P$28_P$28") (pintype "passive"))
      (node (ref "U$3") (pin "P$38") (pinfunction "P$38_P$38") (pintype "passive"))
    )
    (net (code "60") (name "Net-(U$3-PadP$19)") (class "Default")
      (node (ref "U$3") (pin "P$19") (pinfunction "P$19_P$19") (pintype "passive"))
      (node (ref "U$3") (pin "P$29") (pinfunction "P$29_P$29") (pintype "passive"))
      (node (ref "U$3") (pin "P$39") (pinfunction "P$39_P$39") (pintype "passive"))
    )
    (net (code "61") (name "Net-(U$3-PadP$20)") (class "Default")
      (node (ref "U$3") (pin "P$20") (pinfunction "P$20_P$20") (pintype "passive"))
      (node (ref "U$3") (pin "P$30") (pinfunction "P$30_P$30") (pintype "passive"))
      (node (ref "U$3") (pin "P$40") (pinfunction "P$40_P$40") (pintype "passive"))
    )
    (net (code "62") (name "Net-(U$3-PadP$41)") (class "Default")
      (node (ref "U$3") (pin "P$41") (pinfunction "P$41_P$41") (pintype "passive"))
      (node (ref "U$3") (pin "P$42") (pinfunction "P$42_P$42") (pintype "passive"))
      (node (ref "U$3") (pin "P$43") (pinfunction "P$43_P$43") (pintype "passive"))
      (node (ref "U$3") (pin "P$44") (pinfunction "P$44_P$44") (pintype "passive"))
      (node (ref "U$3") (pin "P$45") (pinfunction "P$45_P$45") (pintype "passive"))
      (node (ref "U$3") (pin "P$46") (pinfunction "P$46_P$46") (pintype "passive"))
      (node (ref "U$3") (pin "P$47") (pinfunction "P$47_P$47") (pintype "passive"))
      (node (ref "U$3") (pin "P$48") (pinfunction "P$48_P$48") (pintype "passive"))
      (node (ref "U$3") (pin "P$49") (pinfunction "P$49_P$49") (pintype "passive"))
      (node (ref "U$3") (pin "P$50") (pinfunction "P$50_P$50") (pintype "passive"))
    )
    (net (code "63") (name "Net-(U$3-PadP$51)") (class "Default")
      (node (ref "U$3") (pin "P$51") (pinfunction "P$51_P$51") (pintype "passive"))
      (node (ref "U$3") (pin "P$52") (pinfunction "P$52_P$52") (pintype "passive"))
      (node (ref "U$3") (pin "P$53") (pinfunction "P$53_P$53") (pintype "passive"))
      (node (ref "U$3") (pin "P$54") (pinfunction "P$54_P$54") (pintype "passive"))
      (node (ref "U$3") (pin "P$55") (pinfunction "P$55_P$55") (pintype "passive"))
      (node (ref "U$3") (pin "P$56") (pinfunction "P$56_P$56") (pintype "passive"))
      (node (ref "U$3") (pin "P$57") (pinfunction "P$57_P$57") (pintype "passive"))
      (node (ref "U$3") (pin "P$58") (pinfunction "P$58_P$58") (pintype "passive"))
      (node (ref "U$3") (pin "P$59") (pinfunction "P$59_P$59") (pintype "passive"))
      (node (ref "U$3") (pin "P$60") (pinfunction "P$60_P$60") (pintype "passive"))
    )
    (net (code "64") (name "Net-(U$3-PadP$61)") (class "Default")
      (node (ref "U$3") (pin "P$61") (pinfunction "P$61_P$61") (pintype "passive"))
      (node (ref "U$3") (pin "P$71") (pinfunction "P$71_P$71") (pintype "passive"))
      (node (ref "U$3") (pin "P$81") (pinfunction "P$81_P$81") (pintype "passive"))
      (node (ref "U$3") (pin "P$91") (pinfunction "P$91_P$91") (pintype "passive"))
    )
    (net (code "65") (name "Net-(U$3-PadP$62)") (class "Default")
      (node (ref "U$3") (pin "P$62") (pinfunction "P$62_P$62") (pintype "passive"))
      (node (ref "U$3") (pin "P$72") (pinfunction "P$72_P$72") (pintype "passive"))
      (node (ref "U$3") (pin "P$82") (pinfunction "P$82_P$82") (pintype "passive"))
      (node (ref "U$3") (pin "P$92") (pinfunction "P$92_P$92") (pintype "passive"))
    )
    (net (code "66") (name "Net-(U$3-PadP$63)") (class "Default")
      (node (ref "U$3") (pin "P$63") (pinfunction "P$63_P$63") (pintype "passive"))
      (node (ref "U$3") (pin "P$73") (pinfunction "P$73_P$73") (pintype "passive"))
      (node (ref "U$3") (pin "P$83") (pinfunction "P$83_P$83") (pintype "passive"))
      (node (ref "U$3") (pin "P$93") (pinfunction "P$93_P$93") (pintype "passive"))
    )
    (net (code "67") (name "Net-(U$3-PadP$64)") (class "Default")
      (node (ref "U$3") (pin "P$64") (pinfunction "P$64_P$64") (pintype "passive"))
      (node (ref "U$3") (pin "P$74") (pinfunction "P$74_P$74") (pintype "passive"))
      (node (ref "U$3") (pin "P$84") (pinfunction "P$84_P$84") (pintype "passive"))
      (node (ref "U$3") (pin "P$94") (pinfunction "P$94_P$94") (pintype "passive"))
    )
    (net (code "68") (name "Net-(U$3-PadP$65)") (class "Default")
      (node (ref "U$3") (pin "P$65") (pinfunction "P$65_P$65") (pintype "passive"))
      (node (ref "U$3") (pin "P$75") (pinfunction "P$75_P$75") (pintype "passive"))
      (node (ref "U$3") (pin "P$85") (pinfunction "P$85_P$85") (pintype "passive"))
      (node (ref "U$3") (pin "P$95") (pinfunction "P$95_P$95") (pintype "passive"))
    )
    (net (code "69") (name "Net-(U$3-PadP$66)") (class "Default")
      (node (ref "U$3") (pin "P$66") (pinfunction "P$66_P$66") (pintype "passive"))
      (node (ref "U$3") (pin "P$76") (pinfunction "P$76_P$76") (pintype "passive"))
      (node (ref "U$3") (pin "P$86") (pinfunction "P$86_P$86") (pintype "passive"))
      (node (ref "U$3") (pin "P$96") (pinfunction "P$96_P$96") (pintype "passive"))
    )
    (net (code "70") (name "Net-(U$3-PadP$67)") (class "Default")
      (node (ref "U$3") (pin "P$67") (pinfunction "P$67_P$67") (pintype "passive"))
      (node (ref "U$3") (pin "P$77") (pinfunction "P$77_P$77") (pintype "passive"))
      (node (ref "U$3") (pin "P$87") (pinfunction "P$87_P$87") (pintype "passive"))
      (node (ref "U$3") (pin "P$97") (pinfunction "P$97_P$97") (pintype "passive"))
    )
    (net (code "71") (name "Net-(U$3-PadP$68)") (class "Default")
      (node (ref "U$3") (pin "P$68") (pinfunction "P$68_P$68") (pintype "passive"))
      (node (ref "U$3") (pin "P$78") (pinfunction "P$78_P$78") (pintype "passive"))
      (node (ref "U$3") (pin "P$88") (pinfunction "P$88_P$88") (pintype "passive"))
      (node (ref "U$3") (pin "P$98") (pinfunction "P$98_P$98") (pintype "passive"))
    )
    (net (code "72") (name "Net-(U$3-PadP$69)") (class "Default")
      (node (ref "U$3") (pin "P$69") (pinfunction "P$69_P$69") (pintype "passive"))
      (node (ref "U$3") (pin "P$79") (pinfunction "P$79_P$79") (pintype "passive"))
      (node (ref "U$3") (pin "P$89") (pinfunction "P$89_P$89") (pintype "passive"))
      (node (ref "U$3") (pin "P$99") (pinfunction "P$99_P$99") (pintype "passive"))
    )
    (net (code "73") (name "Net-(U$3-PadP$100)") (class "Default")
      (node (ref "U$3") (pin "P$100") (pinfunction "P$100_P$100") (pintype "passive"))
      (node (ref "U$3") (pin "P$70") (pinfunction "P$70_P$70") (pintype "passive"))
      (node (ref "U$3") (pin "P$80") (pinfunction "P$80_P$80") (pintype "passive"))
      (node (ref "U$3") (pin "P$90") (pinfunction "P$90_P$90") (pintype "passive"))
    )
    (net (code "74") (name "Net-(U$4-Pad1)") (class "Default")
      (node (ref "U$4") (pin "1") (pinfunction "1_1") (pintype "bidirectional"))
      (node (ref "U$4") (pin "2") (pinfunction "2_2") (pintype "bidirectional"))
      (node (ref "U$4") (pin "3") (pinfunction "3_3") (pintype "bidirectional"))
    )
    (net (code "75") (name "Net-(U$5-Pad1)") (class "Default")
      (node (ref "U$5") (pin "1") (pinfunction "1_1") (pintype "bidirectional"))
      (node (ref "U$5") (pin "2") (pinfunction "2_2") (pintype "bidirectional"))
      (node (ref "U$5") (pin "3") (pinfunction "3_3") (pintype "bidirectional"))
    )
    (net (code "76") (name "Net-(U$6-Pad1)") (class "Default")
      (node (ref "U$6") (pin "1") (pinfunction "1_1") (pintype "bidirectional"))
      (node (ref "U$6") (pin "2") (pinfunction "2_2") (pintype "bidirectional"))
      (node (ref "U$6") (pin "3") (pinfunction "3_3") (pintype "bidirectional"))
    )
    (net (code "77") (name "Net-(U$7-Pad1)") (class "Default")
      (node (ref "U$7") (pin "1") (pinfunction "1_1") (pintype "bidirectional"))
      (node (ref "U$7") (pin "2") (pinfunction "2_2") (pintype "bidirectional"))
      (node (ref "U$7") (pin "3") (pinfunction "3_3") (pintype "bidirectional"))
    )
    (net (code "78") (name "Net-(U$8-Pad1)") (class "Default")
      (node (ref "U$8") (pin "1") (pinfunction "1_1") (pintype "bidirectional"))
      (node (ref "U$8") (pin "2") (pinfunction "2_2") (pintype "bidirectional"))
      (node (ref "U$8") (pin "3") (pinfunction "3_3") (pintype "bidirectional"))
    )
    (net (code "79") (name "Net-(U$9-Pad1)") (class "Default")
      (node (ref "U$9") (pin "1") (pinfunction "1_1") (pintype "bidirectional"))
      (node (ref "U$9") (pin "2") (pinfunction "2_2") (pintype "bidirectional"))
      (node (ref "U$9") (pin "3") (pinfunction "3_3") (pintype "bidirectional"))
    )
    (net (code "80") (name "Net-(U$10-Pad1)") (class "Default")
      (node (ref "U$10") (pin "1") (pinfunction "1_1") (pintype "bidirectional"))
      (node (ref "U$10") (pin "2") (pinfunction "2_2") (pintype "bidirectional"))
      (node (ref "U$10") (pin "3") (pinfunction "3_3") (pintype "bidirectional"))
    )
    (net (code "81") (name "Net-(U$11-Pad1)") (class "Default")
      (node (ref "U$11") (pin "1") (pinfunction "1_1") (pintype "bidirectional"))
      (node (ref "U$11") (pin "2") (pinfunction "2_2") (pintype "bidirectional"))
      (node (ref "U$11") (pin "3") (pinfunction "3_3") (pintype "bidirectional"))
    )
    (net (code "82") (name "Net-(U$12-Pad1)") (class "Default")
      (node (ref "U$12") (pin "1") (pinfunction "1_1") (pintype "bidirectional"))
      (node (ref "U$12") (pin "2") (pinfunction "2_2") (pintype "bidirectional"))
      (node (ref "U$12") (pin "3") (pinfunction "3_3") (pintype "bidirectional"))
    )
    (net (code "83") (name "Net-(U$13-Pad1)") (class "Default")
      (node (ref "U$13") (pin "1") (pinfunction "1_1") (pintype "bidirectional"))
      (node (ref "U$13") (pin "2") (pinfunction "2_2") (pintype "bidirectional"))
      (node (ref "U$13") (pin "3") (pinfunction "3_3") (pintype "bidirectional"))
    )
    (net (code "84") (name "Net-(U$14-Pad1)") (class "Default")
      (node (ref "U$14") (pin "1") (pinfunction "1_1") (pintype "bidirectional"))
      (node (ref "U$14") (pin "2") (pinfunction "2_2") (pintype "bidirectional"))
      (node (ref "U$14") (pin "3") (pinfunction "3_3") (pintype "bidirectional"))
    )
    (net (code "85") (name "Net-(U$15-Pad1)") (class "Default")
      (node (ref "U$15") (pin "1") (pinfunction "1_1") (pintype "bidirectional"))
      (node (ref "U$15") (pin "2") (pinfunction "2_2") (pintype "bidirectional"))
      (node (ref "U$15") (pin "3") (pinfunction "3_3") (pintype "bidirectional"))
    )
    (net (code "86") (name "Net-(U$16-Pad1)") (class "Default")
      (node (ref "U$16") (pin "1") (pinfunction "1_1") (pintype "bidirectional"))
      (node (ref "U$16") (pin "2") (pinfunction "2_2") (pintype "bidirectional"))
      (node (ref "U$16") (pin "3") (pinfunction "3_3") (pintype "bidirectional"))
    )
    (net (code "87") (name "Net-(U$17-Pad1)") (class "Default")
      (node (ref "U$17") (pin "1") (pinfunction "1_1") (pintype "bidirectional"))
      (node (ref "U$17") (pin "2") (pinfunction "2_2") (pintype "bidirectional"))
      (node (ref "U$17") (pin "3") (pinfunction "3_3") (pintype "bidirectional"))
    )
    (net (code "88") (name "Net-(U$18-Pad1)") (class "Default")
      (node (ref "U$18") (pin "1") (pinfunction "1_1") (pintype "bidirectional"))
      (node (ref "U$18") (pin "2") (pinfunction "2_2") (pintype "bidirectional"))
      (node (ref "U$18") (pin "3") (pinfunction "3_3") (pintype "bidirectional"))
    )
    (net (code "89") (name "Net-(U$19-Pad1)") (class "Default")
      (node (ref "U$19") (pin "1") (pinfunction "1_1") (pintype "bidirectional"))
      (node (ref "U$19") (pin "2") (pinfunction "2_2") (pintype "bidirectional"))
      (node (ref "U$19") (pin "3") (pinfunction "3_3") (pintype "bidirectional"))
    )
    (net (code "90") (name "VCC") (class "Default")
      (node (ref "C2") (pin "1") (pinfunction "+_1") (pintype "passive"))
      (node (ref "D1") (pin "C") (pinfunction "C_C") (pintype "passive"))
      (node (ref "IC1") (pin "7") (pinfunction "VCC_7") (pintype "bidirectional"))
      (node (ref "IC2") (pin "3") (pinfunction "VO_3") (pintype "passive"))
      (node (ref "J3") (pin "2") (pinfunction "2_2") (pintype "passive"))
      (node (ref "JP1") (pin "2") (pinfunction "2_2") (pintype "passive"))
      (node (ref "R1") (pin "1") (pinfunction "1_1") (pintype "passive"))
      (node (ref "R2") (pin "2") (pinfunction "2_2") (pintype "passive"))
      (node (ref "U$1") (pin "P$1") (pinfunction "1_P$1") (pintype "passive"))
      (node (ref "U$1") (pin "P$10") (pinfunction "P$10_P$10") (pintype "passive"))
      (node (ref "U$1") (pin "P$2") (pinfunction "5_P$2") (pintype "passive"))
      (node (ref "U$1") (pin "P$3") (pinfunction "P$3_P$3") (pintype "passive"))
      (node (ref "U$1") (pin "P$4") (pinfunction "P$4_P$4") (pintype "passive"))
      (node (ref "U$1") (pin "P$5") (pinfunction "P$5_P$5") (pintype "passive"))
      (node (ref "U$1") (pin "P$6") (pinfunction "P$6_P$6") (pintype "passive"))
      (node (ref "U$1") (pin "P$7") (pinfunction "P$7_P$7") (pintype "passive"))
      (node (ref "U$1") (pin "P$8") (pinfunction "P$8_P$8") (pintype "passive"))
      (node (ref "U$1") (pin "P$9") (pinfunction "P$9_P$9") (pintype "passive"))
      (node (ref "VCC") (pin "1") (pinfunction "1_1") (pintype "passive"))
      (node (ref "VCC") (pin "2") (pinfunction "2_2") (pintype "passive"))
      (node (ref "VCC") (pin "3") (pinfunction "3_3") (pintype "passive"))
    )
    (net (code "91") (name "VIN") (class "Default")
      (node (ref "C1") (pin "1") (pinfunction "+_1") (pintype "passive"))
      (node (ref "IC2") (pin "1") (pinfunction "VI_1") (pintype "input"))
      (node (ref "JP1") (pin "1") (pinfunction "1_1") (pintype "passive"))
      (node (ref "JP2") (pin "2") (pinfunction "2_2") (pintype "passive"))
      (node (ref "VIN_") (pin "1") (pinfunction "1_1") (pintype "passive"))
      (node (ref "VIN_") (pin "2") (pinfunction "2_2") (pintype "passive"))
      (node (ref "VIN_") (pin "3") (pinfunction "3_3") (pintype "passive"))
    )
    (net (code "92") (name "unconnected-(S1-O-Pad1)") (class "Default")
      (node (ref "S1") (pin "1") (pinfunction "O_1") (pintype "passive"))
    )
    (net (code "93") (name "unconnected-(U$2-GNDBREAK-PadGND@2)") (class "Default")
      (node (ref "U$2") (pin "GND@2") (pinfunction "GNDBREAK_GND@2") (pintype "bidirectional"))
    )
  )
)
